# PIC_Processor.net
KiCad netlist of a schematic drawn in Altium Designer
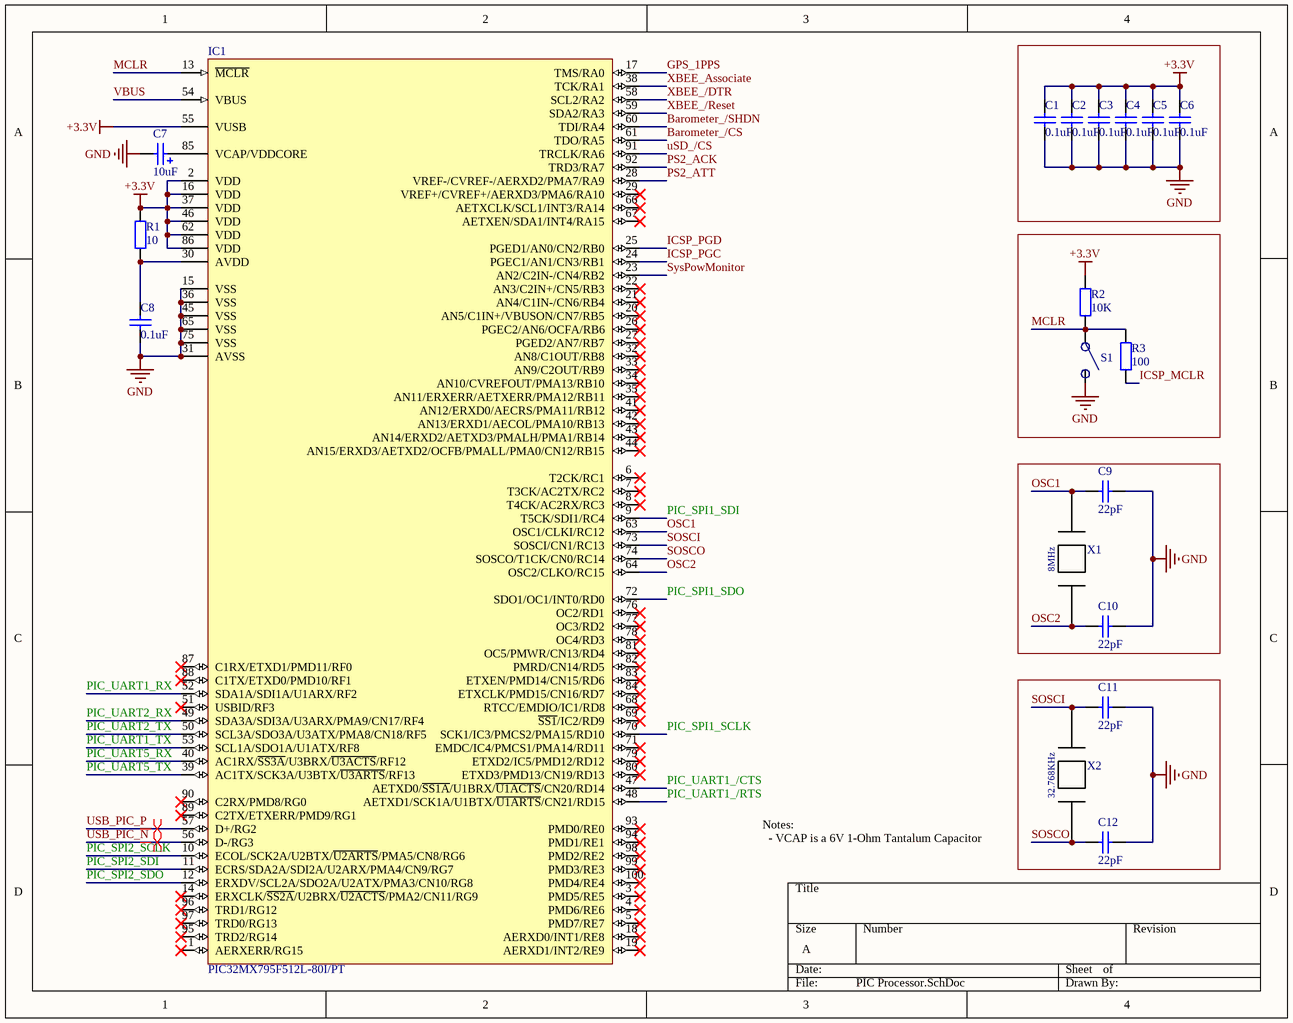
[diagram p0: PIC Processor.SchDoc]

(export (version "E")
  (design (tool "Eeschema 10.0.6"))
  (components
    (comp (ref "C1")
      (value "0.1uF")
      (footprint "SMD 1206")
      (description "Capacitor")
      (fields (field (name "Comment") "0.1uF SMD 1206"))
      (libsource (lib "Miscellaneous Devices") (part "Cap"))
    )
    (comp (ref "C2")
      (value "0.1uF")
      (footprint "SMD 1206")
      (description "Capacitor")
      (fields (field (name "Comment") "0.1uF SMD 1206"))
      (libsource (lib "Miscellaneous Devices") (part "Cap"))
    )
    (comp (ref "C3")
      (value "0.1uF")
      (footprint "SMD 1206")
      (description "Capacitor")
      (fields (field (name "Comment") "0.1uF SMD 1206"))
      (libsource (lib "Miscellaneous Devices") (part "Cap"))
    )
    (comp (ref "C4")
      (value "0.1uF")
      (footprint "SMD 1206")
      (description "Capacitor")
      (fields (field (name "Comment") "0.1uF SMD 1206"))
      (libsource (lib "Miscellaneous Devices") (part "Cap"))
    )
    (comp (ref "C5")
      (value "0.1uF")
      (footprint "SMD 1206")
      (description "Capacitor")
      (fields (field (name "Comment") "0.1uF SMD 1206"))
      (libsource (lib "Miscellaneous Devices") (part "Cap"))
    )
    (comp (ref "C6")
      (value "0.1uF")
      (footprint "SMD 1206")
      (description "Capacitor")
      (fields (field (name "Comment") "0.1uF SMD 1206"))
      (libsource (lib "Miscellaneous Devices") (part "Cap"))
    )
    (comp (ref "C7")
      (value "10uF")
      (footprint "Capacitor - Tantalum Case A")
      (description "Tantalum Capacitor - Case A")
      (fields (field (name "Comment") "10uF Low-ESR Tantalum CaseA"))
      (libsource (lib "Ad-Flier_Parts") (part "SMD_Cap_Tantalum"))
    )
    (comp (ref "C8")
      (value "0.1uF")
      (footprint "SMD 1206")
      (description "Capacitor")
      (fields (field (name "Comment") "0.1uF SMD 1206"))
      (libsource (lib "Miscellaneous Devices") (part "Cap"))
    )
    (comp (ref "C9")
      (value "22pF")
      (footprint "SMD 1206")
      (description "Capacitor")
      (fields (field (name "Comment") "22pF SMD 1206"))
      (libsource (lib "Miscellaneous Devices") (part "Cap"))
    )
    (comp (ref "C10")
      (value "22pF")
      (footprint "SMD 1206")
      (description "Capacitor")
      (fields (field (name "Comment") "22pF SMD 1206"))
      (libsource (lib "Miscellaneous Devices") (part "Cap"))
    )
    (comp (ref "C11")
      (value "22pF")
      (footprint "SMD 1206")
      (description "Capacitor")
      (fields (field (name "Comment") "22pF SMD 1206"))
      (libsource (lib "Miscellaneous Devices") (part "Cap"))
    )
    (comp (ref "C12")
      (value "22pF")
      (footprint "SMD 1206")
      (description "Capacitor")
      (fields (field (name "Comment") "22pF SMD 1206"))
      (libsource (lib "Miscellaneous Devices") (part "Cap"))
    )
    (comp (ref "IC1")
      (value "PIC32MX795F512L-80I/PT")
      (footprint "TQFP-PF100_L")
      (fields (field (name "PUBLISHER") "Altium Limited"))
      (libsource (lib "Microchip Microcontroller 32-Bit PIC32") (part "PIC32MX795F512L-80I/PT"))
    )
    (comp (ref "R1")
      (value "10")
      (footprint "SMD 0805")
      (description "Resistor")
      (fields (field (name "Comment") "10 SMD 0805"))
      (libsource (lib "Miscellaneous Devices") (part "Res2"))
    )
    (comp (ref "R2")
      (value "10K")
      (footprint "SMD 0805")
      (description "Resistor")
      (fields (field (name "Comment") "10K SMD 0805"))
      (libsource (lib "Miscellaneous Devices") (part "Res2"))
    )
    (comp (ref "R3")
      (value "100")
      (footprint "SMD 0805")
      (description "Resistor")
      (fields (field (name "Comment") "100 SMD 0805"))
      (libsource (lib "") (part "Res2_1"))
    )
    (comp (ref "S1")
      (value "Reset")
      (footprint "SMD Tactile Switch")
      (description "SMD Tactile Switch")
      (libsource (lib "Ad-Flier_Parts") (part "SMD Tactile Switch"))
    )
    (comp (ref "X1")
      (value "XT9M20ANA8M")
      (footprint "XT9M20ANA8M - 8MHz Capacitor")
      (description "8MHz SMD Crystal")
      (libsource (lib "Ad-Flier_Parts") (part "XT9M20ANA8M"))
    )
    (comp (ref "X2")
      (value "SSP-T6-7PF-20PPM")
      (footprint "32.768KHz Crystal")
      (description "32.768KHz 7pF SMD Crystal")
      (libsource (lib "Ad-Flier_Parts") (part "SSP-T6-7PF-20PPM"))
    )
  )
  (nets
    (net (code "1") (name "+3.3V") (class "Default")
      (node (ref "C1") (pin "1") (pinfunction "1_1") (pintype "passive"))
      (node (ref "C2") (pin "1") (pinfunction "1_1") (pintype "passive"))
      (node (ref "C3") (pin "1") (pinfunction "1_1") (pintype "passive"))
      (node (ref "C4") (pin "1") (pinfunction "1_1") (pintype "passive"))
      (node (ref "C5") (pin "1") (pinfunction "1_1") (pintype "passive"))
      (node (ref "C6") (pin "1") (pinfunction "1_1") (pintype "passive"))
      (node (ref "IC1") (pin "16") (pinfunction "VDD_16") (pintype "power_in"))
      (node (ref "IC1") (pin "2") (pinfunction "VDD_2") (pintype "power_in"))
      (node (ref "IC1") (pin "37") (pinfunction "VDD_37") (pintype "power_in"))
      (node (ref "IC1") (pin "46") (pinfunction "VDD_46") (pintype "power_in"))
      (node (ref "IC1") (pin "55") (pinfunction "VUSB_55") (pintype "power_in"))
      (node (ref "IC1") (pin "62") (pinfunction "VDD_62") (pintype "power_in"))
      (node (ref "IC1") (pin "86") (pinfunction "VDD_86") (pintype "power_in"))
      (node (ref "R1") (pin "2") (pinfunction "2_2") (pintype "passive"))
      (node (ref "R2") (pin "2") (pinfunction "2_2") (pintype "passive"))
    )
    (net (code "2") (name "/Barometer_{slash}CS") (class "Default")
      (node (ref "IC1") (pin "61") (pinfunction "TDO/RA5_61") (pintype "bidirectional"))
    )
    (net (code "3") (name "/Barometer_{slash}SHDN") (class "Default")
      (node (ref "IC1") (pin "60") (pinfunction "TDI/RA4_60") (pintype "bidirectional"))
    )
    (net (code "4") (name "/GPS_1PPS") (class "Default")
      (node (ref "IC1") (pin "17") (pinfunction "TMS/RA0_17") (pintype "bidirectional"))
    )
    (net (code "5") (name "/ICSP_MCLR") (class "Default")
      (node (ref "R3") (pin "2") (pinfunction "2_2") (pintype "passive"))
    )
    (net (code "6") (name "/ICSP_PGC") (class "Default")
      (node (ref "IC1") (pin "24") (pinfunction "PGEC1/AN1/CN3/RB1_24") (pintype "bidirectional"))
    )
    (net (code "7") (name "/ICSP_PGD") (class "Default")
      (node (ref "IC1") (pin "25") (pinfunction "PGED1/AN0/CN2/RB0_25") (pintype "bidirectional"))
    )
    (net (code "8") (name "/MCLR") (class "Default")
      (node (ref "IC1") (pin "13") (pinfunction "~{MCLR}_13") (pintype "input"))
      (node (ref "R2") (pin "1") (pinfunction "1_1") (pintype "passive"))
      (node (ref "R3") (pin "1") (pinfunction "1_1") (pintype "passive"))
      (node (ref "S1") (pin "2") (pintype "passive"))
    )
    (net (code "9") (name "/OSC1") (class "Default")
      (node (ref "C9") (pin "2") (pinfunction "2_2") (pintype "passive"))
      (node (ref "IC1") (pin "63") (pinfunction "OSC1/CLKI/RC12_63") (pintype "bidirectional"))
      (node (ref "X1") (pin "1") (pinfunction "0_1") (pintype "passive"))
    )
    (net (code "10") (name "/OSC2") (class "Default")
      (node (ref "C10") (pin "2") (pinfunction "2_2") (pintype "passive"))
      (node (ref "IC1") (pin "64") (pinfunction "OSC2/CLKO/RC15_64") (pintype "bidirectional"))
      (node (ref "X1") (pin "0") (pinfunction "0_0") (pintype "passive"))
    )
    (net (code "11") (name "/PIC_SPI1_SCLK") (class "Default")
      (node (ref "IC1") (pin "70") (pinfunction "SCK1/IC3/PMCS2/PMA15/RD10_70") (pintype "bidirectional"))
    )
    (net (code "12") (name "/PIC_SPI1_SDI") (class "Default")
      (node (ref "IC1") (pin "9") (pinfunction "T5CK/SDI1/RC4_9") (pintype "bidirectional"))
    )
    (net (code "13") (name "/PIC_SPI1_SDO") (class "Default")
      (node (ref "IC1") (pin "72") (pinfunction "SDO1/OC1/INT0/RD0_72") (pintype "bidirectional"))
    )
    (net (code "14") (name "/PIC_SPI2_SCLK") (class "Default")
      (node (ref "IC1") (pin "10") (pinfunction "ECOL/SCK2A/U2BTX/~{U2ARTS}/PMA5/CN8/RG6_10") (pintype "bidirectional"))
    )
    (net (code "15") (name "/PIC_SPI2_SDI") (class "Default")
      (node (ref "IC1") (pin "11") (pinfunction "ECRS/SDA2A/SDI2A/U2ARX/PMA4/CN9/RG7_11") (pintype "bidirectional"))
    )
    (net (code "16") (name "/PIC_SPI2_SDO") (class "Default")
      (node (ref "IC1") (pin "12") (pinfunction "ERXDV/SCL2A/SDO2A/U2ATX/PMA3/CN10/RG8_12") (pintype "bidirectional"))
    )
    (net (code "17") (name "/PIC_UART1_RX") (class "Default")
      (node (ref "IC1") (pin "52") (pinfunction "SDA1A/SDI1A/U1ARX/RF2_52") (pintype "bidirectional"))
    )
    (net (code "18") (name "/PIC_UART1_TX") (class "Default")
      (node (ref "IC1") (pin "53") (pinfunction "SCL1A/SDO1A/U1ATX/RF8_53") (pintype "bidirectional"))
    )
    (net (code "19") (name "/PIC_UART1_{slash}CTS") (class "Default")
      (node (ref "IC1") (pin "47") (pinfunction "AETXD0/~{SS1A}/U1BRX/~{U1ACTS}/CN20/RD14_47") (pintype "bidirectional"))
    )
    (net (code "20") (name "/PIC_UART1_{slash}RTS") (class "Default")
      (node (ref "IC1") (pin "48") (pinfunction "AETXD1/SCK1A/U1BTX/~{U1ARTS}/CN21/RD15_48") (pintype "bidirectional"))
    )
    (net (code "21") (name "/PIC_UART2_RX") (class "Default")
      (node (ref "IC1") (pin "49") (pinfunction "SDA3A/SDI3A/U3ARX/PMA9/CN17/RF4_49") (pintype "bidirectional"))
    )
    (net (code "22") (name "/PIC_UART2_TX") (class "Default")
      (node (ref "IC1") (pin "50") (pinfunction "SCL3A/SDO3A/U3ATX/PMA8/CN18/RF5_50") (pintype "bidirectional"))
    )
    (net (code "23") (name "/PIC_UART5_RX") (class "Default")
      (node (ref "IC1") (pin "40") (pinfunction "AC1RX/~{SS3A}/U3BRX/~{U3ACTS}/RF12_40") (pintype "bidirectional"))
    )
    (net (code "24") (name "/PIC_UART5_TX") (class "Default")
      (node (ref "IC1") (pin "39") (pinfunction "AC1TX/SCK3A/U3BTX/~{U3ARTS}/RF13_39") (pintype "bidirectional"))
    )
    (net (code "25") (name "/PS2_ACK") (class "Default")
      (node (ref "IC1") (pin "92") (pinfunction "TRD3/RA7_92") (pintype "bidirectional"))
    )
    (net (code "26") (name "/PS2_ATT") (class "Default")
      (node (ref "IC1") (pin "28") (pinfunction "VREF-/CVREF-/AERXD2/PMA7/RA9_28") (pintype "bidirectional"))
    )
    (net (code "27") (name "/SOSCI") (class "Default")
      (node (ref "C11") (pin "2") (pinfunction "2_2") (pintype "passive"))
      (node (ref "IC1") (pin "73") (pinfunction "SOSCI/CN1/RC13_73") (pintype "bidirectional"))
      (node (ref "X2") (pin "0") (pinfunction "2_0") (pintype "passive"))
    )
    (net (code "28") (name "/SOSCO") (class "Default")
      (node (ref "C12") (pin "2") (pinfunction "2_2") (pintype "passive"))
      (node (ref "IC1") (pin "74") (pinfunction "SOSCO/T1CK/CN0/RC14_74") (pintype "bidirectional"))
      (node (ref "X2") (pin "1") (pinfunction "2_1") (pintype "passive"))
    )
    (net (code "29") (name "/SysPowMonitor") (class "Default")
      (node (ref "IC1") (pin "23") (pinfunction "AN2/C2IN-/CN4/RB2_23") (pintype "bidirectional"))
    )
    (net (code "30") (name "/USB_PIC_N") (class "Default")
      (node (ref "IC1") (pin "56") (pinfunction "D-/RG3_56") (pintype "bidirectional"))
    )
    (net (code "31") (name "/USB_PIC_P") (class "Default")
      (node (ref "IC1") (pin "57") (pinfunction "D+/RG2_57") (pintype "bidirectional"))
    )
    (net (code "32") (name "/VBUS") (class "Default")
      (node (ref "IC1") (pin "54") (pinfunction "VBUS_54") (pintype "input"))
    )
    (net (code "33") (name "/XBEE_Associate") (class "Default")
      (node (ref "IC1") (pin "38") (pinfunction "TCK/RA1_38") (pintype "bidirectional"))
    )
    (net (code "34") (name "/XBEE_{slash}DTR") (class "Default")
      (node (ref "IC1") (pin "58") (pinfunction "SCL2/RA2_58") (pintype "bidirectional"))
    )
    (net (code "35") (name "/XBEE_{slash}Reset") (class "Default")
      (node (ref "IC1") (pin "59") (pinfunction "SDA2/RA3_59") (pintype "bidirectional"))
    )
    (net (code "36") (name "/uSD_{slash}CS") (class "Default")
      (node (ref "IC1") (pin "91") (pinfunction "TRCLK/RA6_91") (pintype "bidirectional"))
    )
    (net (code "37") (name "GND") (class "Default")
      (node (ref "C1") (pin "2") (pinfunction "2_2") (pintype "passive"))
      (node (ref "C10") (pin "1") (pinfunction "1_1") (pintype "passive"))
      (node (ref "C11") (pin "1") (pinfunction "1_1") (pintype "passive"))
      (node (ref "C12") (pin "1") (pinfunction "1_1") (pintype "passive"))
      (node (ref "C2") (pin "2") (pinfunction "2_2") (pintype "passive"))
      (node (ref "C3") (pin "2") (pinfunction "2_2") (pintype "passive"))
      (node (ref "C4") (pin "2") (pinfunction "2_2") (pintype "passive"))
      (node (ref "C5") (pin "2") (pinfunction "2_2") (pintype "passive"))
      (node (ref "C6") (pin "2") (pinfunction "2_2") (pintype "passive"))
      (node (ref "C7") (pin "2") (pinfunction "-_2") (pintype "passive"))
      (node (ref "C8") (pin "2") (pinfunction "2_2") (pintype "passive"))
      (node (ref "C9") (pin "1") (pinfunction "1_1") (pintype "passive"))
      (node (ref "IC1") (pin "15") (pinfunction "VSS_15") (pintype "power_in"))
      (node (ref "IC1") (pin "31") (pinfunction "AVSS_31") (pintype "power_in"))
      (node (ref "IC1") (pin "36") (pinfunction "VSS_36") (pintype "power_in"))
      (node (ref "IC1") (pin "45") (pinfunction "VSS_45") (pintype "power_in"))
      (node (ref "IC1") (pin "65") (pinfunction "VSS_65") (pintype "power_in"))
      (node (ref "IC1") (pin "75") (pinfunction "VSS_75") (pintype "power_in"))
      (node (ref "S1") (pin "1") (pintype "passive"))
    )
    (net (code "38") (name "Net-(C7-+)") (class "Default")
      (node (ref "C7") (pin "1") (pinfunction "+_1") (pintype "passive"))
      (node (ref "IC1") (pin "85") (pinfunction "VCAP/VDDCORE_85") (pintype "power_in"))
    )
    (net (code "39") (name "Net-(IC1-AVDD)") (class "Default")
      (node (ref "C8") (pin "1") (pinfunction "1_1") (pintype "passive"))
      (node (ref "IC1") (pin "30") (pinfunction "AVDD_30") (pintype "power_in"))
      (node (ref "R1") (pin "1") (pinfunction "1_1") (pintype "passive"))
    )
    (net (code "40") (name "unconnected-(IC1-AERXD0{slash}INT1{slash}RE8-Pad18)") (class "Default")
      (node (ref "IC1") (pin "18") (pinfunction "AERXD0/INT1/RE8_18") (pintype "bidirectional+no_connect"))
    )
    (net (code "41") (name "unconnected-(IC1-AERXD1{slash}INT2{slash}RE9-Pad19)") (class "Default")
      (node (ref "IC1") (pin "19") (pinfunction "AERXD1/INT2/RE9_19") (pintype "bidirectional+no_connect"))
    )
    (net (code "42") (name "unconnected-(IC1-AERXERR{slash}RG15-Pad1)") (class "Default")
      (node (ref "IC1") (pin "1") (pinfunction "AERXERR/RG15_1") (pintype "bidirectional+no_connect"))
    )
    (net (code "43") (name "unconnected-(IC1-AETXCLK{slash}SCL1{slash}INT3{slash}RA14-Pad66)") (class "Default")
      (node (ref "IC1") (pin "66") (pinfunction "AETXCLK/SCL1/INT3/RA14_66") (pintype "bidirectional+no_connect"))
    )
    (net (code "44") (name "unconnected-(IC1-AETXEN{slash}SDA1{slash}INT4{slash}RA15-Pad67)") (class "Default")
      (node (ref "IC1") (pin "67") (pinfunction "AETXEN/SDA1/INT4/RA15_67") (pintype "bidirectional+no_connect"))
    )
    (net (code "45") (name "unconnected-(IC1-AN3{slash}C2IN+{slash}CN5{slash}RB3-Pad22)") (class "Default")
      (node (ref "IC1") (pin "22") (pinfunction "AN3/C2IN+/CN5/RB3_22") (pintype "bidirectional+no_connect"))
    )
    (net (code "46") (name "unconnected-(IC1-AN4{slash}C1IN-{slash}CN6{slash}RB4-Pad21)") (class "Default")
      (node (ref "IC1") (pin "21") (pinfunction "AN4/C1IN-/CN6/RB4_21") (pintype "bidirectional+no_connect"))
    )
    (net (code "47") (name "unconnected-(IC1-AN5{slash}C1IN+{slash}VBUSON{slash}CN7{slash}RB5-Pad20)") (class "Default")
      (node (ref "IC1") (pin "20") (pinfunction "AN5/C1IN+/VBUSON/CN7/RB5_20") (pintype "bidirectional+no_connect"))
    )
    (net (code "48") (name "unconnected-(IC1-AN8{slash}C1OUT{slash}RB8-Pad32)") (class "Default")
      (node (ref "IC1") (pin "32") (pinfunction "AN8/C1OUT/RB8_32") (pintype "bidirectional+no_connect"))
    )
    (net (code "49") (name "unconnected-(IC1-AN9{slash}C2OUT{slash}RB9-Pad33)") (class "Default")
      (node (ref "IC1") (pin "33") (pinfunction "AN9/C2OUT/RB9_33") (pintype "bidirectional+no_connect"))
    )
    (net (code "50") (name "unconnected-(IC1-AN10{slash}CVREFOUT{slash}PMA13{slash}RB10-Pad34)") (class "Default")
      (node (ref "IC1") (pin "34") (pinfunction "AN10/CVREFOUT/PMA13/RB10_34") (pintype "bidirectional+no_connect"))
    )
    (net (code "51") (name "unconnected-(IC1-AN11{slash}ERXERR{slash}AETXERR{slash}PMA12{slash}RB11-Pad35)") (class "Default")
      (node (ref "IC1") (pin "35") (pinfunction "AN11/ERXERR/AETXERR/PMA12/RB11_35") (pintype "bidirectional+no_connect"))
    )
    (net (code "52") (name "unconnected-(IC1-AN12{slash}ERXD0{slash}AECRS{slash}PMA11{slash}RB12-Pad41)") (class "Default")
      (node (ref "IC1") (pin "41") (pinfunction "AN12/ERXD0/AECRS/PMA11/RB12_41") (pintype "bidirectional+no_connect"))
    )
    (net (code "53") (name "unconnected-(IC1-AN13{slash}ERXD1{slash}AECOL{slash}PMA10{slash}RB13-Pad42)") (class "Default")
      (node (ref "IC1") (pin "42") (pinfunction "AN13/ERXD1/AECOL/PMA10/RB13_42") (pintype "bidirectional+no_connect"))
    )
    (net (code "54") (name "unconnected-(IC1-AN14{slash}ERXD2{slash}AETXD3{slash}PMALH{slash}PMA1{slash}RB14-Pad43)") (class "Default")
      (node (ref "IC1") (pin "43") (pinfunction "AN14/ERXD2/AETXD3/PMALH/PMA1/RB14_43") (pintype "bidirectional+no_connect"))
    )
    (net (code "55") (name "unconnected-(IC1-AN15{slash}ERXD3{slash}AETXD2{slash}OCFB{slash}PMALL{slash}PMA0{slash}CN12{slash}RB15-Pad44)") (class "Default")
      (node (ref "IC1") (pin "44") (pinfunction "AN15/ERXD3/AETXD2/OCFB/PMALL/PMA0/CN12/RB15_44") (pintype "bidirectional+no_connect"))
    )
    (net (code "56") (name "unconnected-(IC1-C1RX{slash}ETXD1{slash}PMD11{slash}RF0-Pad87)") (class "Default")
      (node (ref "IC1") (pin "87") (pinfunction "C1RX/ETXD1/PMD11/RF0_87") (pintype "bidirectional+no_connect"))
    )
    (net (code "57") (name "unconnected-(IC1-C1TX{slash}ETXD0{slash}PMD10{slash}RF1-Pad88)") (class "Default")
      (node (ref "IC1") (pin "88") (pinfunction "C1TX/ETXD0/PMD10/RF1_88") (pintype "bidirectional+no_connect"))
    )
    (net (code "58") (name "unconnected-(IC1-C2RX{slash}PMD8{slash}RG0-Pad90)") (class "Default")
      (node (ref "IC1") (pin "90") (pinfunction "C2RX/PMD8/RG0_90") (pintype "bidirectional+no_connect"))
    )
    (net (code "59") (name "unconnected-(IC1-C2TX{slash}ETXERR{slash}PMD9{slash}RG1-Pad89)") (class "Default")
      (node (ref "IC1") (pin "89") (pinfunction "C2TX/ETXERR/PMD9/RG1_89") (pintype "bidirectional+no_connect"))
    )
    (net (code "60") (name "unconnected-(IC1-EMDC{slash}IC4{slash}PMCS1{slash}PMA14{slash}RD11-Pad71)") (class "Default")
      (node (ref "IC1") (pin "71") (pinfunction "EMDC/IC4/PMCS1/PMA14/RD11_71") (pintype "bidirectional+no_connect"))
    )
    (net (code "61") (name "unconnected-(IC1-ERXCLK{slash}~{SS2A}{slash}U2BRX{slash}~{U2ACTS}{slash}PMA2{slash}CN11{slash}RG9-Pad14)") (class "Default")
      (node (ref "IC1") (pin "14") (pinfunction "ERXCLK/~{SS2A}/U2BRX/~{U2ACTS}/PMA2/CN11/RG9_14") (pintype "bidirectional+no_connect"))
    )
    (net (code "62") (name "unconnected-(IC1-ETXCLK{slash}PMD15{slash}CN16{slash}RD7-Pad84)") (class "Default")
      (node (ref "IC1") (pin "84") (pinfunction "ETXCLK/PMD15/CN16/RD7_84") (pintype "bidirectional+no_connect"))
    )
    (net (code "63") (name "unconnected-(IC1-ETXD2{slash}IC5{slash}PMD12{slash}RD12-Pad79)") (class "Default")
      (node (ref "IC1") (pin "79") (pinfunction "ETXD2/IC5/PMD12/RD12_79") (pintype "bidirectional+no_connect"))
    )
    (net (code "64") (name "unconnected-(IC1-ETXD3{slash}PMD13{slash}CN19{slash}RD13-Pad80)") (class "Default")
      (node (ref "IC1") (pin "80") (pinfunction "ETXD3/PMD13/CN19/RD13_80") (pintype "bidirectional+no_connect"))
    )
    (net (code "65") (name "unconnected-(IC1-ETXEN{slash}PMD14{slash}CN15{slash}RD6-Pad83)") (class "Default")
      (node (ref "IC1") (pin "83") (pinfunction "ETXEN/PMD14/CN15/RD6_83") (pintype "bidirectional+no_connect"))
    )
    (net (code "66") (name "unconnected-(IC1-OC2{slash}RD1-Pad76)") (class "Default")
      (node (ref "IC1") (pin "76") (pinfunction "OC2/RD1_76") (pintype "bidirectional+no_connect"))
    )
    (net (code "67") (name "unconnected-(IC1-OC3{slash}RD2-Pad77)") (class "Default")
      (node (ref "IC1") (pin "77") (pinfunction "OC3/RD2_77") (pintype "bidirectional+no_connect"))
    )
    (net (code "68") (name "unconnected-(IC1-OC4{slash}RD3-Pad78)") (class "Default")
      (node (ref "IC1") (pin "78") (pinfunction "OC4/RD3_78") (pintype "bidirectional+no_connect"))
    )
    (net (code "69") (name "unconnected-(IC1-OC5{slash}PMWR{slash}CN13{slash}RD4-Pad81)") (class "Default")
      (node (ref "IC1") (pin "81") (pinfunction "OC5/PMWR/CN13/RD4_81") (pintype "bidirectional+no_connect"))
    )
    (net (code "70") (name "unconnected-(IC1-PGEC2{slash}AN6{slash}OCFA{slash}RB6-Pad26)") (class "Default")
      (node (ref "IC1") (pin "26") (pinfunction "PGEC2/AN6/OCFA/RB6_26") (pintype "bidirectional+no_connect"))
    )
    (net (code "71") (name "unconnected-(IC1-PGED2{slash}AN7{slash}RB7-Pad27)") (class "Default")
      (node (ref "IC1") (pin "27") (pinfunction "PGED2/AN7/RB7_27") (pintype "bidirectional+no_connect"))
    )
    (net (code "72") (name "unconnected-(IC1-PMD0{slash}RE0-Pad93)") (class "Default")
      (node (ref "IC1") (pin "93") (pinfunction "PMD0/RE0_93") (pintype "bidirectional+no_connect"))
    )
    (net (code "73") (name "unconnected-(IC1-PMD1{slash}RE1-Pad94)") (class "Default")
      (node (ref "IC1") (pin "94") (pinfunction "PMD1/RE1_94") (pintype "bidirectional+no_connect"))
    )
    (net (code "74") (name "unconnected-(IC1-PMD2{slash}RE2-Pad98)") (class "Default")
      (node (ref "IC1") (pin "98") (pinfunction "PMD2/RE2_98") (pintype "bidirectional+no_connect"))
    )
    (net (code "75") (name "unconnected-(IC1-PMD3{slash}RE3-Pad99)") (class "Default")
      (node (ref "IC1") (pin "99") (pinfunction "PMD3/RE3_99") (pintype "bidirectional+no_connect"))
    )
    (net (code "76") (name "unconnected-(IC1-PMD4{slash}RE4-Pad100)") (class "Default")
      (node (ref "IC1") (pin "100") (pinfunction "PMD4/RE4_100") (pintype "bidirectional+no_connect"))
    )
    (net (code "77") (name "unconnected-(IC1-PMD5{slash}RE5-Pad3)") (class "Default")
      (node (ref "IC1") (pin "3") (pinfunction "PMD5/RE5_3") (pintype "bidirectional+no_connect"))
    )
    (net (code "78") (name "unconnected-(IC1-PMD6{slash}RE6-Pad4)") (class "Default")
      (node (ref "IC1") (pin "4") (pinfunction "PMD6/RE6_4") (pintype "bidirectional+no_connect"))
    )
    (net (code "79") (name "unconnected-(IC1-PMD7{slash}RE7-Pad5)") (class "Default")
      (node (ref "IC1") (pin "5") (pinfunction "PMD7/RE7_5") (pintype "bidirectional+no_connect"))
    )
    (net (code "80") (name "unconnected-(IC1-PMRD{slash}CN14{slash}RD5-Pad82)") (class "Default")
      (node (ref "IC1") (pin "82") (pinfunction "PMRD/CN14/RD5_82") (pintype "bidirectional+no_connect"))
    )
    (net (code "81") (name "unconnected-(IC1-RTCC{slash}EMDIO{slash}IC1{slash}RD8-Pad68)") (class "Default")
      (node (ref "IC1") (pin "68") (pinfunction "RTCC/EMDIO/IC1/RD8_68") (pintype "bidirectional+no_connect"))
    )
    (net (code "82") (name "unconnected-(IC1-T2CK{slash}RC1-Pad6)") (class "Default")
      (node (ref "IC1") (pin "6") (pinfunction "T2CK/RC1_6") (pintype "bidirectional+no_connect"))
    )
    (net (code "83") (name "unconnected-(IC1-T3CK{slash}AC2TX{slash}RC2-Pad7)") (class "Default")
      (node (ref "IC1") (pin "7") (pinfunction "T3CK/AC2TX/RC2_7") (pintype "bidirectional+no_connect"))
    )
    (net (code "84") (name "unconnected-(IC1-T4CK{slash}AC2RX{slash}RC3-Pad8)") (class "Default")
      (node (ref "IC1") (pin "8") (pinfunction "T4CK/AC2RX/RC3_8") (pintype "bidirectional+no_connect"))
    )
    (net (code "85") (name "unconnected-(IC1-TRD0{slash}RG13-Pad97)") (class "Default")
      (node (ref "IC1") (pin "97") (pinfunction "TRD0/RG13_97") (pintype "bidirectional+no_connect"))
    )
    (net (code "86") (name "unconnected-(IC1-TRD1{slash}RG12-Pad96)") (class "Default")
      (node (ref "IC1") (pin "96") (pinfunction "TRD1/RG12_96") (pintype "bidirectional+no_connect"))
    )
    (net (code "87") (name "unconnected-(IC1-TRD2{slash}RG14-Pad95)") (class "Default")
      (node (ref "IC1") (pin "95") (pinfunction "TRD2/RG14_95") (pintype "bidirectional+no_connect"))
    )
    (net (code "88") (name "unconnected-(IC1-USBID{slash}RF3-Pad51)") (class "Default")
      (node (ref "IC1") (pin "51") (pinfunction "USBID/RF3_51") (pintype "bidirectional+no_connect"))
    )
    (net (code "89") (name "unconnected-(IC1-VREF+{slash}CVREF+{slash}AERXD3{slash}PMA6{slash}RA10-Pad29)") (class "Default")
      (node (ref "IC1") (pin "29") (pinfunction "VREF+/CVREF+/AERXD3/PMA6/RA10_29") (pintype "bidirectional+no_connect"))
    )
    (net (code "90") (name "unconnected-(IC1-~{SS1}{slash}IC2{slash}RD9-Pad69)") (class "Default")
      (node (ref "IC1") (pin "69") (pinfunction "~{SS1}/IC2/RD9_69") (pintype "bidirectional+no_connect"))
    )
  )
)
